# mainSheet.net
KiCad netlist of a schematic drawn in Altium Designer
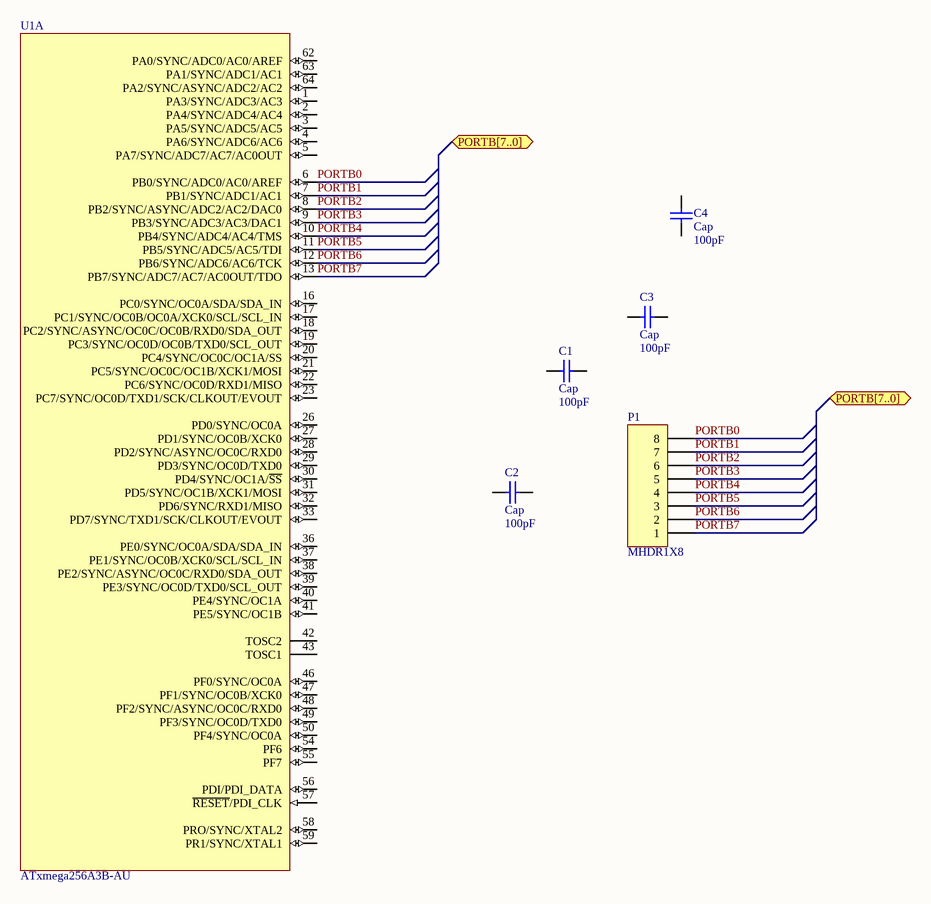
[diagram p0: mainSheet.SchDoc]

(export (version "E")
  (design (tool "Eeschema 10.0.6"))
  (components
    (comp (ref "C1")
      (value "Cap")
      (footprint "RAD-0.3")
      (description "Capacitor")
      (fields (field (name "ALTIUM_VALUE") "100pF") (field (name "PUBLISHER") "Altium Limited"))
      (libsource (lib "Miscellaneous Devices") (part "Cap"))
    )
    (comp (ref "C2")
      (value "Cap")
      (footprint "RAD-0.3")
      (description "Capacitor")
      (fields (field (name "ALTIUM_VALUE") "100pF") (field (name "PUBLISHER") "Altium Limited"))
      (libsource (lib "Miscellaneous Devices") (part "Cap"))
    )
    (comp (ref "C3")
      (value "Cap")
      (footprint "RAD-0.3")
      (description "Capacitor")
      (fields (field (name "ALTIUM_VALUE") "100pF") (field (name "PUBLISHER") "Altium Limited"))
      (libsource (lib "Miscellaneous Devices") (part "Cap"))
    )
    (comp (ref "C4")
      (value "Cap")
      (footprint "RAD-0.3")
      (description "Capacitor")
      (fields (field (name "ALTIUM_VALUE") "100pF") (field (name "PUBLISHER") "Altium Limited"))
      (libsource (lib "Miscellaneous Devices") (part "Cap"))
    )
    (comp (ref "P1")
      (value "MHDR1X8")
      (footprint "MHDR1X8")
      (description "Header, 8-Pin")
      (fields (field (name "PUBLISHER") "Altium Limited"))
      (libsource (lib "Miscellaneous Connectors") (part "MHDR1X8"))
    )
    (comp (ref "U1")
      (value "ATxmega256A3B-AU")
      (footprint "64A_N")
      (fields (field (name "PUBLISHER") "Altium Limited"))
      (libsource (lib "Atmel Microcontroller 8-16-Bit AVR XMEGA") (part "ATxmega256A3B-AU"))
    )
  )
  (nets
    (net (code "1") (name "/PORTB0") (class "Default")
      (node (ref "P1") (pin "8") (pinfunction "8_8") (pintype "passive"))
      (node (ref "U1") (pin "6") (pinfunction "PB0/SYNC/ADC0/AC0/AREF_6") (pintype "bidirectional"))
    )
    (net (code "2") (name "/PORTB1") (class "Default")
      (node (ref "P1") (pin "7") (pinfunction "7_7") (pintype "passive"))
      (node (ref "U1") (pin "7") (pinfunction "PB1/SYNC/ADC1/AC1_7") (pintype "bidirectional"))
    )
    (net (code "3") (name "/PORTB2") (class "Default")
      (node (ref "P1") (pin "6") (pinfunction "6_6") (pintype "passive"))
      (node (ref "U1") (pin "8") (pinfunction "PB2/SYNC/ASYNC/ADC2/AC2/DAC0_8") (pintype "bidirectional"))
    )
    (net (code "4") (name "/PORTB3") (class "Default")
      (node (ref "P1") (pin "5") (pinfunction "5_5") (pintype "passive"))
      (node (ref "U1") (pin "9") (pinfunction "PB3/SYNC/ADC3/AC3/DAC1_9") (pintype "bidirectional"))
    )
    (net (code "5") (name "/PORTB4") (class "Default")
      (node (ref "P1") (pin "4") (pinfunction "4_4") (pintype "passive"))
      (node (ref "U1") (pin "10") (pinfunction "PB4/SYNC/ADC4/AC4/TMS_10") (pintype "bidirectional"))
    )
    (net (code "6") (name "/PORTB5") (class "Default")
      (node (ref "P1") (pin "3") (pinfunction "3_3") (pintype "passive"))
      (node (ref "U1") (pin "11") (pinfunction "PB5/SYNC/ADC5/AC5/TDI_11") (pintype "bidirectional"))
    )
    (net (code "7") (name "/PORTB6") (class "Default")
      (node (ref "P1") (pin "2") (pinfunction "2_2") (pintype "passive"))
      (node (ref "U1") (pin "12") (pinfunction "PB6/SYNC/ADC6/AC6/TCK_12") (pintype "bidirectional"))
    )
    (net (code "8") (name "/PORTB7") (class "Default")
      (node (ref "P1") (pin "1") (pinfunction "1_1") (pintype "passive"))
      (node (ref "U1") (pin "13") (pinfunction "PB7/SYNC/ADC7/AC7/AC0OUT/TDO_13") (pintype "bidirectional"))
    )
    (net (code "10") (name "unconnected-(C1-Pad1)") (class "Default")
      (node (ref "C1") (pin "1") (pinfunction "1_1") (pintype "passive"))
    )
    (net (code "11") (name "unconnected-(C1-Pad2)") (class "Default")
      (node (ref "C1") (pin "2") (pinfunction "2_2") (pintype "passive"))
    )
    (net (code "12") (name "unconnected-(C2-Pad1)") (class "Default")
      (node (ref "C2") (pin "1") (pinfunction "1_1") (pintype "passive"))
    )
    (net (code "13") (name "unconnected-(C2-Pad2)") (class "Default")
      (node (ref "C2") (pin "2") (pinfunction "2_2") (pintype "passive"))
    )
    (net (code "14") (name "unconnected-(C3-Pad1)") (class "Default")
      (node (ref "C3") (pin "1") (pinfunction "1_1") (pintype "passive"))
    )
    (net (code "15") (name "unconnected-(C3-Pad2)") (class "Default")
      (node (ref "C3") (pin "2") (pinfunction "2_2") (pintype "passive"))
    )
    (net (code "16") (name "unconnected-(C4-Pad1)") (class "Default")
      (node (ref "C4") (pin "1") (pinfunction "1_1") (pintype "passive"))
    )
    (net (code "17") (name "unconnected-(C4-Pad2)") (class "Default")
      (node (ref "C4") (pin "2") (pinfunction "2_2") (pintype "passive"))
    )
    (net (code "18") (name "unconnected-(U1A-PA0{slash}SYNC{slash}ADC0{slash}AC0{slash}AREF-Pad62)") (class "Default")
      (node (ref "U1") (pin "62") (pinfunction "PA0/SYNC/ADC0/AC0/AREF_62") (pintype "bidirectional"))
    )
    (net (code "19") (name "unconnected-(U1A-PA1{slash}SYNC{slash}ADC1{slash}AC1-Pad63)") (class "Default")
      (node (ref "U1") (pin "63") (pinfunction "PA1/SYNC/ADC1/AC1_63") (pintype "bidirectional"))
    )
    (net (code "20") (name "unconnected-(U1A-PA2{slash}SYNC{slash}ASYNC{slash}ADC2{slash}AC2-Pad64)") (class "Default")
      (node (ref "U1") (pin "64") (pinfunction "PA2/SYNC/ASYNC/ADC2/AC2_64") (pintype "bidirectional"))
    )
    (net (code "21") (name "unconnected-(U1A-PA3{slash}SYNC{slash}ADC3{slash}AC3-Pad1)") (class "Default")
      (node (ref "U1") (pin "1") (pinfunction "PA3/SYNC/ADC3/AC3_1") (pintype "bidirectional"))
    )
    (net (code "22") (name "unconnected-(U1A-PA4{slash}SYNC{slash}ADC4{slash}AC4-Pad2)") (class "Default")
      (node (ref "U1") (pin "2") (pinfunction "PA4/SYNC/ADC4/AC4_2") (pintype "bidirectional"))
    )
    (net (code "23") (name "unconnected-(U1A-PA5{slash}SYNC{slash}ADC5{slash}AC5-Pad3)") (class "Default")
      (node (ref "U1") (pin "3") (pinfunction "PA5/SYNC/ADC5/AC5_3") (pintype "bidirectional"))
    )
    (net (code "24") (name "unconnected-(U1A-PA6{slash}SYNC{slash}ADC6{slash}AC6-Pad4)") (class "Default")
      (node (ref "U1") (pin "4") (pinfunction "PA6/SYNC/ADC6/AC6_4") (pintype "bidirectional"))
    )
    (net (code "25") (name "unconnected-(U1A-PA7{slash}SYNC{slash}ADC7{slash}AC7{slash}AC0OUT-Pad5)") (class "Default")
      (node (ref "U1") (pin "5") (pinfunction "PA7/SYNC/ADC7/AC7/AC0OUT_5") (pintype "bidirectional"))
    )
    (net (code "26") (name "unconnected-(U1A-PC0{slash}SYNC{slash}OC0A{slash}SDA{slash}SDA_IN-Pad16)") (class "Default")
      (node (ref "U1") (pin "16") (pinfunction "PC0/SYNC/OC0A/SDA/SDA_IN_16") (pintype "bidirectional"))
    )
    (net (code "27") (name "unconnected-(U1A-PC1{slash}SYNC{slash}OC0B{slash}OC0A{slash}XCK0{slash}SCL{slash}SCL_IN-Pad17)") (class "Default")
      (node (ref "U1") (pin "17") (pinfunction "PC1/SYNC/OC0B/OC0A/XCK0/SCL/SCL_IN_17") (pintype "bidirectional"))
    )
    (net (code "28") (name "unconnected-(U1A-PC2{slash}SYNC{slash}ASYNC{slash}OC0C{slash}OC0B{slash}RXD0{slash}SDA_OUT-Pad18)") (class "Default")
      (node (ref "U1") (pin "18") (pinfunction "PC2/SYNC/ASYNC/OC0C/OC0B/RXD0/SDA_OUT_18") (pintype "bidirectional"))
    )
    (net (code "29") (name "unconnected-(U1A-PC3{slash}SYNC{slash}OC0D{slash}OC0B{slash}TXD0{slash}SCL_OUT-Pad19)") (class "Default")
      (node (ref "U1") (pin "19") (pinfunction "PC3/SYNC/OC0D/OC0B/TXD0/SCL_OUT_19") (pintype "bidirectional"))
    )
    (net (code "30") (name "unconnected-(U1A-PC4{slash}SYNC{slash}OC0C{slash}OC1A{slash}SS-Pad20)") (class "Default")
      (node (ref "U1") (pin "20") (pinfunction "PC4/SYNC/OC0C/OC1A/SS_20") (pintype "bidirectional"))
    )
    (net (code "31") (name "unconnected-(U1A-PC5{slash}SYNC{slash}OC0C{slash}OC1B{slash}XCK1{slash}MOSI-Pad21)") (class "Default")
      (node (ref "U1") (pin "21") (pinfunction "PC5/SYNC/OC0C/OC1B/XCK1/MOSI_21") (pintype "bidirectional"))
    )
    (net (code "32") (name "unconnected-(U1A-PC6{slash}SYNC{slash}OC0D{slash}RXD1{slash}MISO-Pad22)") (class "Default")
      (node (ref "U1") (pin "22") (pinfunction "PC6/SYNC/OC0D/RXD1/MISO_22") (pintype "bidirectional"))
    )
    (net (code "33") (name "unconnected-(U1A-PC7{slash}SYNC{slash}OC0D{slash}TXD1{slash}SCK{slash}CLKOUT{slash}EVOUT-Pad23)") (class "Default")
      (node (ref "U1") (pin "23") (pinfunction "PC7/SYNC/OC0D/TXD1/SCK/CLKOUT/EVOUT_23") (pintype "bidirectional"))
    )
    (net (code "34") (name "unconnected-(U1A-PD0{slash}SYNC{slash}OC0A-Pad26)") (class "Default")
      (node (ref "U1") (pin "26") (pinfunction "PD0/SYNC/OC0A_26") (pintype "bidirectional"))
    )
    (net (code "35") (name "unconnected-(U1A-PD1{slash}SYNC{slash}OC0B{slash}XCK0-Pad27)") (class "Default")
      (node (ref "U1") (pin "27") (pinfunction "PD1/SYNC/OC0B/XCK0_27") (pintype "bidirectional"))
    )
    (net (code "36") (name "unconnected-(U1A-PD2{slash}SYNC{slash}ASYNC{slash}OC0C{slash}RXD0-Pad28)") (class "Default")
      (node (ref "U1") (pin "28") (pinfunction "PD2/SYNC/ASYNC/OC0C/RXD0_28") (pintype "bidirectional"))
    )
    (net (code "37") (name "unconnected-(U1A-PD3{slash}SYNC{slash}OC0D{slash}TXD0-Pad29)") (class "Default")
      (node (ref "U1") (pin "29") (pinfunction "PD3/SYNC/OC0D/TXD0_29") (pintype "bidirectional"))
    )
    (net (code "38") (name "unconnected-(U1A-PD4{slash}SYNC{slash}OC1A{slash}~{SS}-Pad30)") (class "Default")
      (node (ref "U1") (pin "30") (pinfunction "PD4/SYNC/OC1A/~{SS}_30") (pintype "bidirectional"))
    )
    (net (code "39") (name "unconnected-(U1A-PD5{slash}SYNC{slash}OC1B{slash}XCK1{slash}MOSI-Pad31)") (class "Default")
      (node (ref "U1") (pin "31") (pinfunction "PD5/SYNC/OC1B/XCK1/MOSI_31") (pintype "bidirectional"))
    )
    (net (code "40") (name "unconnected-(U1A-PD6{slash}SYNC{slash}RXD1{slash}MISO-Pad32)") (class "Default")
      (node (ref "U1") (pin "32") (pinfunction "PD6/SYNC/RXD1/MISO_32") (pintype "bidirectional"))
    )
    (net (code "41") (name "unconnected-(U1A-PD7{slash}SYNC{slash}TXD1{slash}SCK{slash}CLKOUT{slash}EVOUT-Pad33)") (class "Default")
      (node (ref "U1") (pin "33") (pinfunction "PD7/SYNC/TXD1/SCK/CLKOUT/EVOUT_33") (pintype "bidirectional"))
    )
    (net (code "42") (name "unconnected-(U1A-PDI{slash}PDI_DATA-Pad56)") (class "Default")
      (node (ref "U1") (pin "56") (pinfunction "PDI/PDI_DATA_56") (pintype "bidirectional"))
    )
    (net (code "43") (name "unconnected-(U1A-PE0{slash}SYNC{slash}OC0A{slash}SDA{slash}SDA_IN-Pad36)") (class "Default")
      (node (ref "U1") (pin "36") (pinfunction "PE0/SYNC/OC0A/SDA/SDA_IN_36") (pintype "bidirectional"))
    )
    (net (code "44") (name "unconnected-(U1A-PE1{slash}SYNC{slash}OC0B{slash}XCK0{slash}SCL{slash}SCL_IN-Pad37)") (class "Default")
      (node (ref "U1") (pin "37") (pinfunction "PE1/SYNC/OC0B/XCK0/SCL/SCL_IN_37") (pintype "bidirectional"))
    )
    (net (code "45") (name "unconnected-(U1A-PE2{slash}SYNC{slash}ASYNC{slash}OC0C{slash}RXD0{slash}SDA_OUT-Pad38)") (class "Default")
      (node (ref "U1") (pin "38") (pinfunction "PE2/SYNC/ASYNC/OC0C/RXD0/SDA_OUT_38") (pintype "bidirectional"))
    )
    (net (code "46") (name "unconnected-(U1A-PE3{slash}SYNC{slash}OC0D{slash}TXD0{slash}SCL_OUT-Pad39)") (class "Default")
      (node (ref "U1") (pin "39") (pinfunction "PE3/SYNC/OC0D/TXD0/SCL_OUT_39") (pintype "bidirectional"))
    )
    (net (code "47") (name "unconnected-(U1A-PE4{slash}SYNC{slash}OC1A-Pad40)") (class "Default")
      (node (ref "U1") (pin "40") (pinfunction "PE4/SYNC/OC1A_40") (pintype "bidirectional"))
    )
    (net (code "48") (name "unconnected-(U1A-PE5{slash}SYNC{slash}OC1B-Pad41)") (class "Default")
      (node (ref "U1") (pin "41") (pinfunction "PE5/SYNC/OC1B_41") (pintype "bidirectional"))
    )
    (net (code "49") (name "unconnected-(U1A-PF0{slash}SYNC{slash}OC0A-Pad46)") (class "Default")
      (node (ref "U1") (pin "46") (pinfunction "PF0/SYNC/OC0A_46") (pintype "bidirectional"))
    )
    (net (code "50") (name "unconnected-(U1A-PF1{slash}SYNC{slash}OC0B{slash}XCK0-Pad47)") (class "Default")
      (node (ref "U1") (pin "47") (pinfunction "PF1/SYNC/OC0B/XCK0_47") (pintype "bidirectional"))
    )
    (net (code "51") (name "unconnected-(U1A-PF2{slash}SYNC{slash}ASYNC{slash}OC0C{slash}RXD0-Pad48)") (class "Default")
      (node (ref "U1") (pin "48") (pinfunction "PF2/SYNC/ASYNC/OC0C/RXD0_48") (pintype "bidirectional"))
    )
    (net (code "52") (name "unconnected-(U1A-PF3{slash}SYNC{slash}OC0D{slash}TXD0-Pad49)") (class "Default")
      (node (ref "U1") (pin "49") (pinfunction "PF3/SYNC/OC0D/TXD0_49") (pintype "bidirectional"))
    )
    (net (code "53") (name "unconnected-(U1A-PF4{slash}SYNC{slash}OC0A-Pad50)") (class "Default")
      (node (ref "U1") (pin "50") (pinfunction "PF4/SYNC/OC0A_50") (pintype "bidirectional"))
    )
    (net (code "54") (name "unconnected-(U1A-PF6-Pad54)") (class "Default")
      (node (ref "U1") (pin "54") (pinfunction "PF6_54") (pintype "bidirectional"))
    )
    (net (code "55") (name "unconnected-(U1A-PF7-Pad55)") (class "Default")
      (node (ref "U1") (pin "55") (pinfunction "PF7_55") (pintype "bidirectional"))
    )
    (net (code "56") (name "unconnected-(U1A-PR1{slash}SYNC{slash}XTAL1-Pad59)") (class "Default")
      (node (ref "U1") (pin "59") (pinfunction "PR1/SYNC/XTAL1_59") (pintype "bidirectional"))
    )
    (net (code "57") (name "unconnected-(U1A-PRO{slash}SYNC{slash}XTAL2-Pad58)") (class "Default")
      (node (ref "U1") (pin "58") (pinfunction "PRO/SYNC/XTAL2_58") (pintype "bidirectional"))
    )
    (net (code "58") (name "unconnected-(U1A-TOSC1-Pad43)") (class "Default")
      (node (ref "U1") (pin "43") (pinfunction "TOSC1_43") (pintype "passive"))
    )
    (net (code "59") (name "unconnected-(U1A-TOSC2-Pad42)") (class "Default")
      (node (ref "U1") (pin "42") (pinfunction "TOSC2_42") (pintype "passive"))
    )
    (net (code "60") (name "unconnected-(U1A-~{RESET}{slash}PDI_CLK-Pad57)") (class "Default")
      (node (ref "U1") (pin "57") (pinfunction "~{RESET}/PDI_CLK_57") (pintype "input"))
    )
  )
)
